# TestBoard2.net
KiCad netlist of a schematic drawn in EAGLE
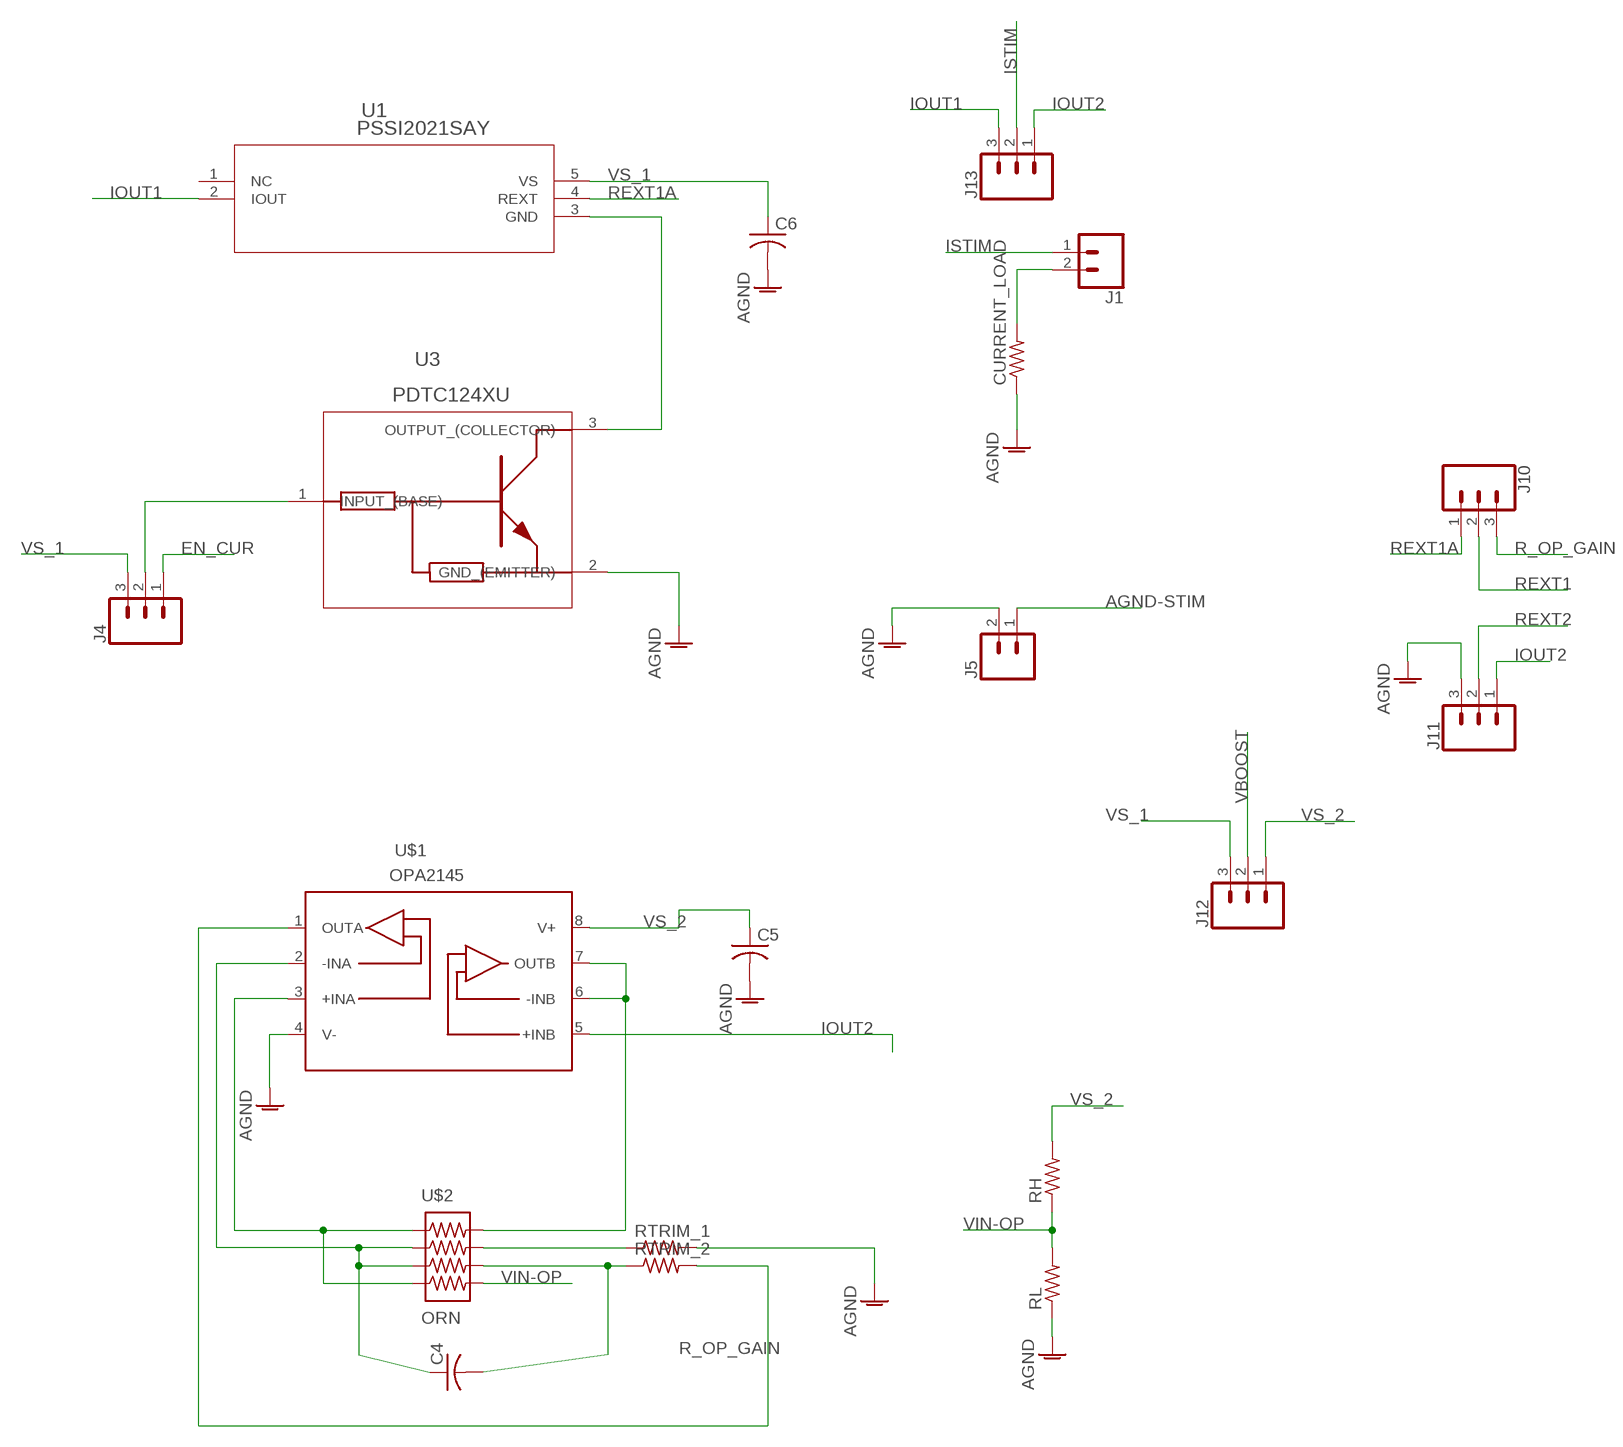
[diagram p0: schematic, sheet 1]
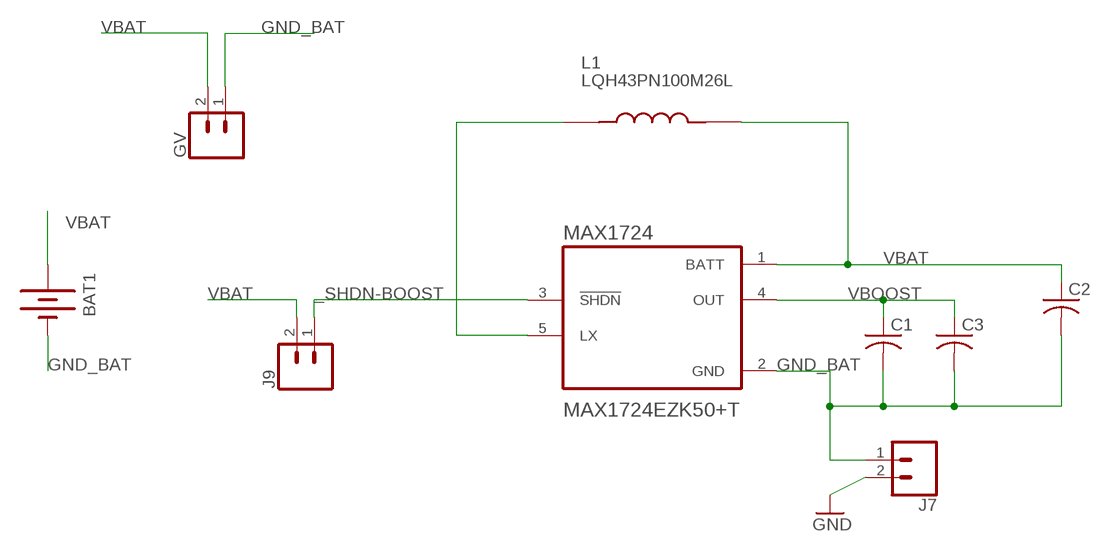
[diagram p1: schematic, sheet 2]
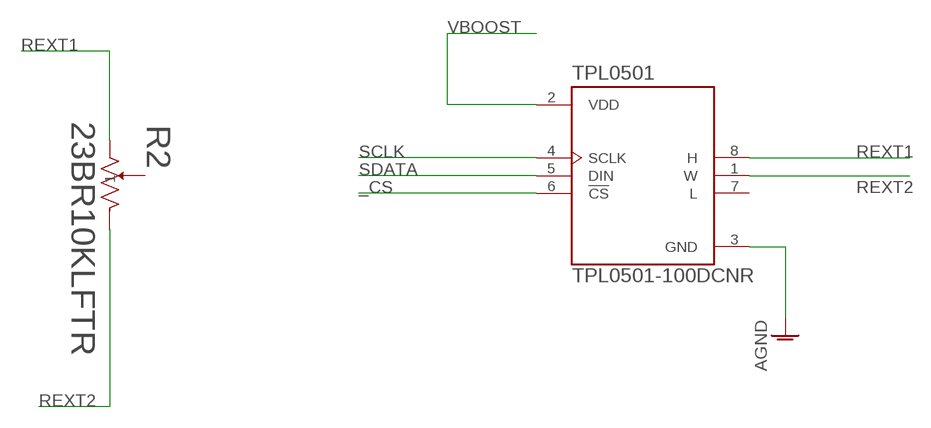
[diagram p2: schematic, sheet 3]
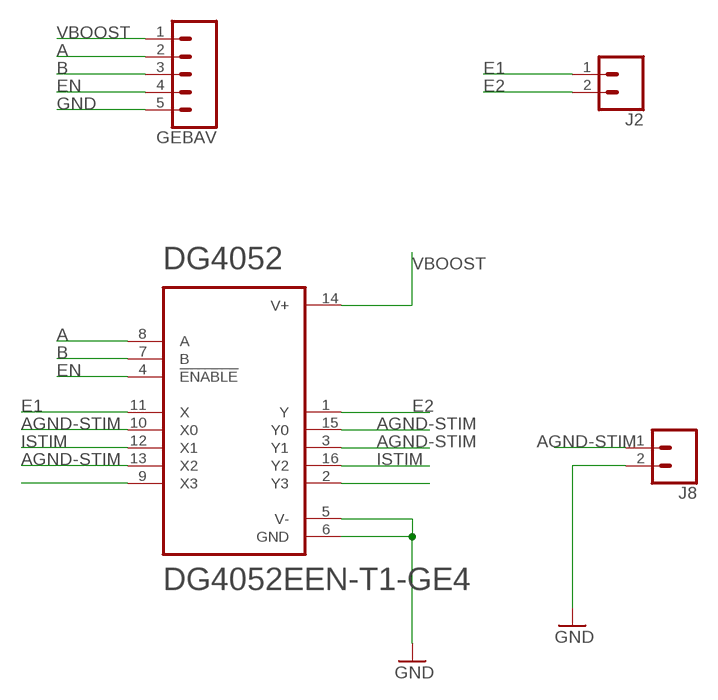
[diagram p3: schematic, sheet 4]
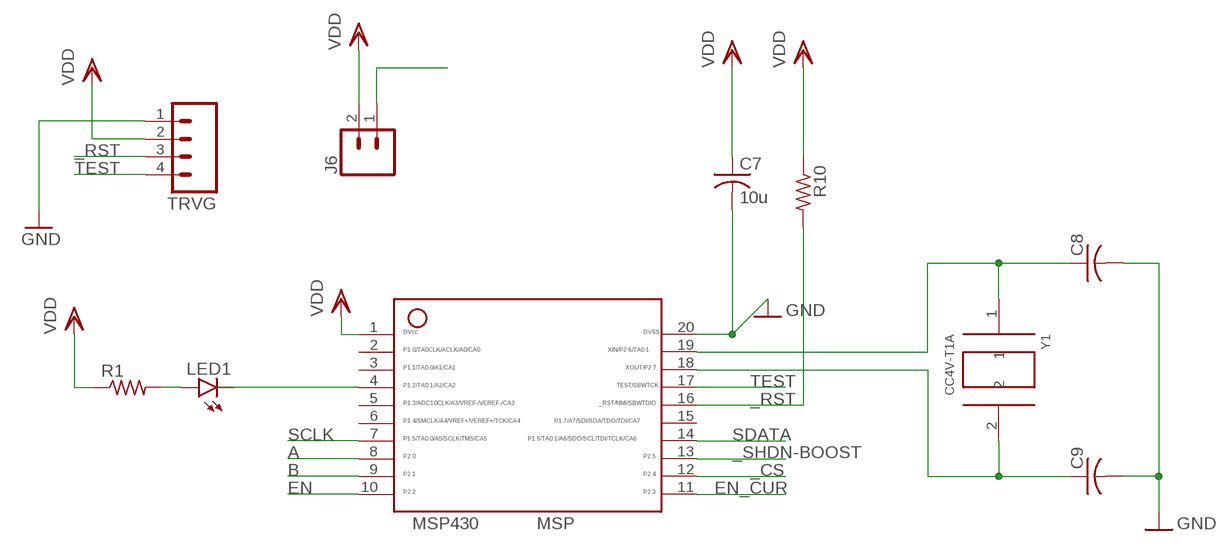
[diagram p4: schematic, sheet 5]

(export (version "E")
  (design (tool "Eeschema 10.0.6"))
  (components
    (comp (ref "BAT1")
      (value "BATTERYBU2032SM")
      (footprint "eagle-import:BU2032SM")
      (libsource (lib "eagle-import") (part "BATTERYBU2032SM"))
    )
    (comp (ref "C1")
      (value "C-USC1206")
      (footprint "eagle-import:C1206")
      (libsource (lib "eagle-import") (part "C-USC1206"))
    )
    (comp (ref "C2")
      (value "C-USC1206")
      (footprint "eagle-import:C1206")
      (libsource (lib "eagle-import") (part "C-USC1206"))
    )
    (comp (ref "C3")
      (value "C-USC0603")
      (footprint "eagle-import:C0603")
      (libsource (lib "eagle-import") (part "C-USC0603"))
    )
    (comp (ref "GV")
      (value "CONN_02")
      (footprint "eagle-import:1X02")
      (libsource (lib "eagle-import") (part "CONN_02"))
    )
    (comp (ref "J7")
      (value "CONN_02")
      (footprint "eagle-import:1X02")
      (libsource (lib "eagle-import") (part "CONN_02"))
    )
    (comp (ref "J9")
      (value "CONN_02")
      (footprint "eagle-import:1X02")
      (libsource (lib "eagle-import") (part "CONN_02"))
    )
    (comp (ref "L1")
      (value "LQH43PN100M26L")
      (footprint "eagle-import:IND_LQH43PN100M26L")
      (fields (field (name "DIGI-KEY_PART_NUMBER") "490-12780-1-ND") (field (name "MF") "Murata"))
      (libsource (lib "eagle-import") (part "LQH43PN100M26L"))
    )
    (comp (ref "MAX1724")
      (value "MAX1724EZK50+T")
      (footprint "eagle-import:SOT95P275X110-5N")
      (fields
        (field (name "DIGI-KEY_PART_NUMBER") "MAX1724EZK50+TCT-ND")
        (field (name "MF") "Maxim Integrated")
      )
      (libsource (lib "eagle-import") (part "MAX1724EZK50+T"))
    )
    (comp (ref "DG4052")
      (value "DG4052EEN-T1-GE4")
      (footprint "eagle-import:QFN40P260X180X60-16N")
      (fields (field (name "DIGI-KEY_PART_NUMBER") "DG4052EEN-T1-GE4CT-ND") (field (name "MF") "Vishay"))
      (libsource (lib "eagle-import") (part "DG4052EEN-T1-GE4"))
    )
    (comp (ref "GEBAV")
      (value "CONN_05LOCK")
      (footprint "eagle-import:1X05_LOCK")
      (libsource (lib "eagle-import") (part "CONN_05LOCK"))
    )
    (comp (ref "J2")
      (value "CONN_02")
      (footprint "eagle-import:1X02")
      (libsource (lib "eagle-import") (part "CONN_02"))
    )
    (comp (ref "J8")
      (value "CONN_02")
      (footprint "eagle-import:1X02")
      (libsource (lib "eagle-import") (part "CONN_02"))
    )
    (comp (ref "C4")
      (value "C-USC0603")
      (footprint "eagle-import:C0603")
      (libsource (lib "eagle-import") (part "C-USC0603"))
    )
    (comp (ref "C5")
      (value "C-USC0603")
      (footprint "eagle-import:C0603")
      (libsource (lib "eagle-import") (part "C-USC0603"))
    )
    (comp (ref "C6")
      (value "C-USC0603")
      (footprint "eagle-import:C0603")
      (libsource (lib "eagle-import") (part "C-USC0603"))
    )
    (comp (ref "CURRENT_LOAD")
      (value "R-US_0204/7")
      (footprint "eagle-import:0204_7")
      (libsource (lib "eagle-import") (part "R-US_0204/7"))
    )
    (comp (ref "J1")
      (value "CONN_02LOCK")
      (footprint "eagle-import:1X02_LOCK")
      (libsource (lib "eagle-import") (part "CONN_02LOCK"))
    )
    (comp (ref "J4")
      (value "CONN_03LOCK")
      (footprint "eagle-import:1X03_LOCK")
      (libsource (lib "eagle-import") (part "CONN_03LOCK"))
    )
    (comp (ref "J5")
      (value "CONN_02")
      (footprint "eagle-import:1X02")
      (libsource (lib "eagle-import") (part "CONN_02"))
    )
    (comp (ref "J10")
      (value "CONN_03")
      (footprint "eagle-import:1X03")
      (libsource (lib "eagle-import") (part "CONN_03"))
    )
    (comp (ref "J11")
      (value "CONN_03")
      (footprint "eagle-import:1X03")
      (libsource (lib "eagle-import") (part "CONN_03"))
    )
    (comp (ref "J12")
      (value "CONN_03LOCK")
      (footprint "eagle-import:1X03_LOCK")
      (libsource (lib "eagle-import") (part "CONN_03LOCK"))
    )
    (comp (ref "J13")
      (value "CONN_03LOCK")
      (footprint "eagle-import:1X03_LOCK")
      (libsource (lib "eagle-import") (part "CONN_03LOCK"))
    )
    (comp (ref "RH")
      (value "R-US_R0603")
      (footprint "eagle-import:R0603")
      (libsource (lib "eagle-import") (part "R-US_R0603"))
    )
    (comp (ref "RL")
      (value "R-US_R0603")
      (footprint "eagle-import:R0603")
      (libsource (lib "eagle-import") (part "R-US_R0603"))
    )
    (comp (ref "RTRIM_1")
      (value "R-US_R0603")
      (footprint "eagle-import:R0603")
      (libsource (lib "eagle-import") (part "R-US_R0603"))
    )
    (comp (ref "RTRIM_2")
      (value "R-US_R0603")
      (footprint "eagle-import:R0603")
      (libsource (lib "eagle-import") (part "R-US_R0603"))
    )
    (comp (ref "U$1")
      (value "OPA2145")
      (footprint "eagle-import:8-VSSOP")
      (libsource (lib "eagle-import") (part "OPA2145"))
    )
    (comp (ref "U$2")
      (value "ORN")
      (footprint "eagle-import:8-TSSOP")
      (libsource (lib "eagle-import") (part "ORN"))
    )
    (comp (ref "U1")
      (value "PSSI2021SAY")
      (footprint "eagle-import:SOT353_NXP")
      (fields (field (name "COPYRIGHT") "Copyright (C) 2021 Ultra Librarian. All rights reserved."))
      (libsource (lib "eagle-import") (part "PSSI2021SAY"))
    )
    (comp (ref "U3")
      (value "PDTC124XU")
      (footprint "eagle-import:SOT323_NXP")
      (fields (field (name "COPYRIGHT") "Copyright (C) 2021 Ultra Librarian. All rights reserved."))
      (libsource (lib "eagle-import") (part "PDTC124XU"))
    )
    (comp (ref "R2")
      (value "23BR10KLFTR")
      (footprint "eagle-import:RES3_23B_TTE")
      (fields (field (name "COPYRIGHT") "Copyright (C) 2016 Accelerated Designs. All rights reserved"))
      (libsource (lib "eagle-import") (part "23BR10KLFTR"))
    )
    (comp (ref "TPL0501")
      (value "TPL0501-100DCNR")
      (footprint "eagle-import:SOT65P280X145-8N")
      (fields (field (name "DIGI-KEY_PART_NUMBER") "296-29584-1-ND") (field (name "MF") "Texas Instruments"))
      (libsource (lib "eagle-import") (part "TPL0501-100DCNR"))
    )
    (comp (ref "C7")
      (value "10u")
      (footprint "eagle-import:C1206")
      (libsource (lib "eagle-import") (part "C-USC1206"))
    )
    (comp (ref "C8")
      (value "C-USC0603")
      (footprint "eagle-import:C0603")
      (libsource (lib "eagle-import") (part "C-USC0603"))
    )
    (comp (ref "C9")
      (value "C-USC0603")
      (footprint "eagle-import:C0603")
      (libsource (lib "eagle-import") (part "C-USC0603"))
    )
    (comp (ref "J6")
      (value "CONN_02")
      (footprint "eagle-import:1X02")
      (libsource (lib "eagle-import") (part "CONN_02"))
    )
    (comp (ref "LED1")
      (value "LEDCHIPLED_0603")
      (footprint "eagle-import:CHIPLED_0603")
      (libsource (lib "eagle-import") (part "LEDCHIPLED_0603"))
    )
    (comp (ref "MSP430")
      (value "MSP")
      (footprint "eagle-import:20_PIN")
      (libsource (lib "eagle-import") (part "MSP430"))
    )
    (comp (ref "R1")
      (value "R-US_R1206")
      (footprint "eagle-import:R1206")
      (libsource (lib "eagle-import") (part "R-US_R1206"))
    )
    (comp (ref "R10")
      (value "R-US_R1206")
      (footprint "eagle-import:R1206")
      (libsource (lib "eagle-import") (part "R-US_R1206"))
    )
    (comp (ref "TRVG")
      (value "M04LOCK")
      (footprint "eagle-import:1X04_LOCK")
      (libsource (lib "eagle-import") (part "M04LOCK"))
    )
    (comp (ref "Y1")
      (value "CC4V-T1A")
      (footprint "eagle-import:CC4V-T1A")
      (fields (field (name "MF") "Micro Crystal AG") (field (name "MP") "CC4V-T1A-32.768KHZ-7PF-20PPM"))
      (libsource (lib "eagle-import") (part "CC4V-T1A"))
    )
  )
  (nets
    (net (code "1") (name "A") (class "Default")
      (node (ref "DG4052") (pin "8") (pinfunction "A_8") (pintype "input"))
      (node (ref "GEBAV") (pin "2") (pinfunction "2_2") (pintype "passive"))
      (node (ref "MSP430") (pin "8") (pinfunction "8_8") (pintype "bidirectional"))
    )
    (net (code "2") (name "AGND") (class "Default")
      (node (ref "C5") (pin "2") (pinfunction "2_2") (pintype "passive"))
      (node (ref "C6") (pin "2") (pinfunction "2_2") (pintype "passive"))
      (node (ref "CURRENT_LOAD") (pin "1") (pinfunction "1_1") (pintype "passive"))
      (node (ref "J11") (pin "3") (pinfunction "3_3") (pintype "passive"))
      (node (ref "J5") (pin "2") (pinfunction "2_2") (pintype "passive"))
      (node (ref "RL") (pin "1") (pinfunction "1_1") (pintype "passive"))
      (node (ref "RTRIM_1") (pin "2") (pinfunction "2_2") (pintype "passive"))
      (node (ref "TPL0501") (pin "3") (pinfunction "GND_3") (pintype "power_in"))
      (node (ref "U$1") (pin "4") (pinfunction "V-_4") (pintype "bidirectional"))
      (node (ref "U3") (pin "2") (pinfunction "GND_(EMITTER)_2") (pintype "passive"))
    )
    (net (code "3") (name "AGND-STIM") (class "Default")
      (node (ref "DG4052") (pin "10") (pinfunction "X0_10") (pintype "passive"))
      (node (ref "DG4052") (pin "13") (pinfunction "X2_13") (pintype "passive"))
      (node (ref "DG4052") (pin "15") (pinfunction "Y0_15") (pintype "passive"))
      (node (ref "DG4052") (pin "3") (pinfunction "Y1_3") (pintype "passive"))
      (node (ref "J5") (pin "1") (pinfunction "1_1") (pintype "passive"))
      (node (ref "J8") (pin "1") (pinfunction "1_1") (pintype "passive"))
    )
    (net (code "4") (name "B") (class "Default")
      (node (ref "DG4052") (pin "7") (pinfunction "B_7") (pintype "input"))
      (node (ref "GEBAV") (pin "3") (pinfunction "3_3") (pintype "passive"))
      (node (ref "MSP430") (pin "9") (pinfunction "9_9") (pintype "bidirectional"))
    )
    (net (code "5") (name "E1") (class "Default")
      (node (ref "DG4052") (pin "11") (pinfunction "X_11") (pintype "passive"))
      (node (ref "J2") (pin "1") (pinfunction "1_1") (pintype "passive"))
    )
    (net (code "6") (name "E2") (class "Default")
      (node (ref "DG4052") (pin "1") (pinfunction "Y_1") (pintype "passive"))
      (node (ref "J2") (pin "2") (pinfunction "2_2") (pintype "passive"))
    )
    (net (code "7") (name "EN") (class "Default")
      (node (ref "DG4052") (pin "4") (pinfunction "~{ENABLE}_4") (pintype "input"))
      (node (ref "GEBAV") (pin "4") (pinfunction "4_4") (pintype "passive"))
      (node (ref "MSP430") (pin "10") (pinfunction "10_10") (pintype "bidirectional"))
    )
    (net (code "8") (name "EN_CUR") (class "Default")
      (node (ref "J4") (pin "1") (pinfunction "1_1") (pintype "passive"))
      (node (ref "MSP430") (pin "11") (pinfunction "11_11") (pintype "bidirectional"))
    )
    (net (code "9") (name "GND") (class "Default")
      (node (ref "C7") (pin "2") (pinfunction "2_2") (pintype "passive"))
      (node (ref "C8") (pin "2") (pinfunction "2_2") (pintype "passive"))
      (node (ref "C9") (pin "2") (pinfunction "2_2") (pintype "passive"))
      (node (ref "DG4052") (pin "5") (pinfunction "V-_5") (pintype "power_in"))
      (node (ref "DG4052") (pin "6") (pinfunction "GND_6") (pintype "power_in"))
      (node (ref "GEBAV") (pin "5") (pinfunction "5_5") (pintype "passive"))
      (node (ref "J7") (pin "2") (pinfunction "2_2") (pintype "passive"))
      (node (ref "J8") (pin "2") (pinfunction "2_2") (pintype "passive"))
      (node (ref "MSP430") (pin "20") (pinfunction "20_20") (pintype "bidirectional"))
      (node (ref "TRVG") (pin "1") (pinfunction "1_1") (pintype "passive"))
    )
    (net (code "10") (name "GND_BAT") (class "Default")
      (node (ref "BAT1") (pin "P$2") (pinfunction "-_P$2") (pintype "power_in"))
      (node (ref "C1") (pin "2") (pinfunction "2_2") (pintype "passive"))
      (node (ref "C2") (pin "2") (pinfunction "2_2") (pintype "passive"))
      (node (ref "C3") (pin "2") (pinfunction "2_2") (pintype "passive"))
      (node (ref "GV") (pin "1") (pinfunction "1_1") (pintype "passive"))
      (node (ref "J7") (pin "1") (pinfunction "1_1") (pintype "passive"))
      (node (ref "MAX1724") (pin "2") (pinfunction "GND_2") (pintype "power_in"))
    )
    (net (code "11") (name "IOUT1") (class "Default")
      (node (ref "J13") (pin "3") (pinfunction "3_3") (pintype "passive"))
      (node (ref "U1") (pin "2") (pinfunction "IOUT_2") (pintype "passive"))
    )
    (net (code "12") (name "IOUT2") (class "Default")
      (node (ref "J11") (pin "1") (pinfunction "1_1") (pintype "passive"))
      (node (ref "J13") (pin "1") (pinfunction "1_1") (pintype "passive"))
      (node (ref "U$1") (pin "5") (pinfunction "+INB_5") (pintype "bidirectional"))
    )
    (net (code "13") (name "ISTIM") (class "Default")
      (node (ref "DG4052") (pin "12") (pinfunction "X1_12") (pintype "passive"))
      (node (ref "DG4052") (pin "16") (pinfunction "Y2_16") (pintype "passive"))
      (node (ref "J1") (pin "1") (pinfunction "1_1") (pintype "passive"))
      (node (ref "J13") (pin "2") (pinfunction "2_2") (pintype "passive"))
    )
    (net (code "14") (name "Net-(C4-Pad2)") (class "Default")
      (node (ref "C4") (pin "2") (pinfunction "2_2") (pintype "passive"))
      (node (ref "RTRIM_2") (pin "1") (pinfunction "1_1") (pintype "passive"))
      (node (ref "U$2") (pin "6") (pinfunction "6_6") (pintype "passive"))
    )
    (net (code "15") (name "Net-(C8-Pad1)") (class "Default")
      (node (ref "C8") (pin "1") (pinfunction "1_1") (pintype "passive"))
      (node (ref "MSP430") (pin "19") (pinfunction "19_19") (pintype "bidirectional"))
      (node (ref "Y1") (pin "1") (pinfunction "1_1") (pintype "passive"))
    )
    (net (code "16") (name "Net-(C9-Pad1)") (class "Default")
      (node (ref "C9") (pin "1") (pinfunction "1_1") (pintype "passive"))
      (node (ref "MSP430") (pin "18") (pinfunction "18_18") (pintype "bidirectional"))
      (node (ref "Y1") (pin "2") (pinfunction "2_2") (pintype "passive"))
    )
    (net (code "17") (name "Net-(CURRENT_LOAD-Pad2)") (class "Default")
      (node (ref "CURRENT_LOAD") (pin "2") (pinfunction "2_2") (pintype "passive"))
      (node (ref "J1") (pin "2") (pinfunction "2_2") (pintype "passive"))
    )
    (net (code "18") (name "Net-(LED1-PadA)") (class "Default")
      (node (ref "LED1") (pin "A") (pinfunction "A_A") (pintype "passive"))
      (node (ref "R1") (pin "2") (pinfunction "2_2") (pintype "passive"))
    )
    (net (code "19") (name "Net-(LED1-PadC)") (class "Default")
      (node (ref "LED1") (pin "C") (pinfunction "C_C") (pintype "passive"))
      (node (ref "MSP430") (pin "4") (pinfunction "4_4") (pintype "bidirectional"))
    )
    (net (code "20") (name "Net-(MAX1724-LX)") (class "Default")
      (node (ref "L1") (pin "1") (pinfunction "1_1") (pintype "passive"))
      (node (ref "MAX1724") (pin "5") (pinfunction "LX_5") (pintype "bidirectional"))
    )
    (net (code "21") (name "Net-(RTRIM_1-Pad1)") (class "Default")
      (node (ref "RTRIM_1") (pin "1") (pinfunction "1_1") (pintype "passive"))
      (node (ref "U$2") (pin "7") (pinfunction "7_7") (pintype "passive"))
    )
    (net (code "22") (name "Net-(U$1-+INA)") (class "Default")
      (node (ref "U$1") (pin "3") (pinfunction "+INA_3") (pintype "bidirectional"))
      (node (ref "U$2") (pin "1") (pinfunction "1_1") (pintype "passive"))
      (node (ref "U$2") (pin "4") (pinfunction "4_4") (pintype "passive"))
    )
    (net (code "23") (name "Net-(U$1--INA)") (class "Default")
      (node (ref "C4") (pin "1") (pinfunction "1_1") (pintype "passive"))
      (node (ref "U$1") (pin "2") (pinfunction "-INA_2") (pintype "bidirectional"))
      (node (ref "U$2") (pin "2") (pinfunction "2_2") (pintype "passive"))
      (node (ref "U$2") (pin "3") (pinfunction "3_3") (pintype "passive"))
    )
    (net (code "24") (name "Net-(U$1--INB)") (class "Default")
      (node (ref "U$1") (pin "6") (pinfunction "-INB_6") (pintype "bidirectional"))
      (node (ref "U$1") (pin "7") (pinfunction "OUTB_7") (pintype "bidirectional"))
      (node (ref "U$2") (pin "8") (pinfunction "8_8") (pintype "passive"))
    )
    (net (code "25") (name "Net-(U1-GND)") (class "Default")
      (node (ref "U1") (pin "3") (pinfunction "GND_3") (pintype "passive"))
      (node (ref "U3") (pin "3") (pinfunction "OUTPUT_(COLLECTOR)_3") (pintype "passive"))
    )
    (net (code "26") (name "Net-(U3-INPUT_(BASE))") (class "Default")
      (node (ref "J4") (pin "2") (pinfunction "2_2") (pintype "passive"))
      (node (ref "U3") (pin "1") (pinfunction "INPUT_(BASE)_1") (pintype "passive"))
    )
    (net (code "27") (name "REXT1") (class "Default")
      (node (ref "J10") (pin "2") (pinfunction "2_2") (pintype "passive"))
      (node (ref "R2") (pin "1") (pinfunction "1_1") (pintype "passive"))
      (node (ref "TPL0501") (pin "8") (pinfunction "H_8") (pintype "bidirectional"))
    )
    (net (code "28") (name "REXT1A") (class "Default")
      (node (ref "J10") (pin "1") (pinfunction "1_1") (pintype "passive"))
      (node (ref "U1") (pin "4") (pinfunction "REXT_4") (pintype "passive"))
    )
    (net (code "29") (name "REXT2") (class "Default")
      (node (ref "J11") (pin "2") (pinfunction "2_2") (pintype "passive"))
      (node (ref "R2") (pin "3") (pinfunction "3_3") (pintype "passive"))
      (node (ref "TPL0501") (pin "1") (pinfunction "W_1") (pintype "bidirectional"))
    )
    (net (code "30") (name "R_OP_GAIN") (class "Default")
      (node (ref "J10") (pin "3") (pinfunction "3_3") (pintype "passive"))
      (node (ref "RTRIM_2") (pin "2") (pinfunction "2_2") (pintype "passive"))
      (node (ref "U$1") (pin "1") (pinfunction "OUTA_1") (pintype "bidirectional"))
    )
    (net (code "31") (name "SCLK") (class "Default")
      (node (ref "MSP430") (pin "7") (pinfunction "7_7") (pintype "bidirectional"))
      (node (ref "TPL0501") (pin "4") (pinfunction "SCLK_4") (pintype "input"))
    )
    (net (code "32") (name "SDATA") (class "Default")
      (node (ref "MSP430") (pin "14") (pinfunction "14_14") (pintype "bidirectional"))
      (node (ref "TPL0501") (pin "5") (pinfunction "DIN_5") (pintype "input"))
    )
    (net (code "33") (name "TEST") (class "Default")
      (node (ref "MSP430") (pin "17") (pinfunction "17_17") (pintype "bidirectional"))
      (node (ref "TRVG") (pin "4") (pinfunction "4_4") (pintype "passive"))
    )
    (net (code "34") (name "VBAT") (class "Default")
      (node (ref "BAT1") (pin "P$1") (pinfunction "+_P$1") (pintype "power_in"))
      (node (ref "C2") (pin "1") (pinfunction "1_1") (pintype "passive"))
      (node (ref "GV") (pin "2") (pinfunction "2_2") (pintype "passive"))
      (node (ref "J6") (pin "1") (pinfunction "1_1") (pintype "passive"))
      (node (ref "J9") (pin "2") (pinfunction "2_2") (pintype "passive"))
      (node (ref "L1") (pin "2") (pinfunction "2_2") (pintype "passive"))
      (node (ref "MAX1724") (pin "1") (pinfunction "BATT_1") (pintype "power_in"))
    )
    (net (code "35") (name "VBOOST") (class "Default")
      (node (ref "C1") (pin "1") (pinfunction "1_1") (pintype "passive"))
      (node (ref "C3") (pin "1") (pinfunction "1_1") (pintype "passive"))
      (node (ref "DG4052") (pin "14") (pinfunction "V+_14") (pintype "power_in"))
      (node (ref "GEBAV") (pin "1") (pinfunction "1_1") (pintype "passive"))
      (node (ref "J12") (pin "2") (pinfunction "2_2") (pintype "passive"))
      (node (ref "MAX1724") (pin "4") (pinfunction "OUT_4") (pintype "output"))
      (node (ref "TPL0501") (pin "2") (pinfunction "VDD_2") (pintype "power_in"))
    )
    (net (code "36") (name "VDD") (class "Default")
      (node (ref "C7") (pin "1") (pinfunction "1_1") (pintype "passive"))
      (node (ref "J6") (pin "2") (pinfunction "2_2") (pintype "passive"))
      (node (ref "MSP430") (pin "1") (pinfunction "1_1") (pintype "bidirectional"))
      (node (ref "R1") (pin "1") (pinfunction "1_1") (pintype "passive"))
      (node (ref "R10") (pin "1") (pinfunction "1_1") (pintype "passive"))
      (node (ref "TRVG") (pin "2") (pinfunction "2_2") (pintype "passive"))
    )
    (net (code "37") (name "VIN-OP") (class "Default")
      (node (ref "RH") (pin "1") (pinfunction "1_1") (pintype "passive"))
      (node (ref "RL") (pin "2") (pinfunction "2_2") (pintype "passive"))
      (node (ref "U$2") (pin "5") (pinfunction "5_5") (pintype "passive"))
    )
    (net (code "38") (name "VS_1") (class "Default")
      (node (ref "C6") (pin "1") (pinfunction "1_1") (pintype "passive"))
      (node (ref "J12") (pin "3") (pinfunction "3_3") (pintype "passive"))
      (node (ref "J4") (pin "3") (pinfunction "3_3") (pintype "passive"))
      (node (ref "U1") (pin "5") (pinfunction "VS_5") (pintype "passive"))
    )
    (net (code "39") (name "VS_2") (class "Default")
      (node (ref "C5") (pin "1") (pinfunction "1_1") (pintype "passive"))
      (node (ref "J12") (pin "1") (pinfunction "1_1") (pintype "passive"))
      (node (ref "RH") (pin "2") (pinfunction "2_2") (pintype "passive"))
      (node (ref "U$1") (pin "8") (pinfunction "V+_8") (pintype "bidirectional"))
    )
    (net (code "40") (name "_CS") (class "Default")
      (node (ref "MSP430") (pin "12") (pinfunction "12_12") (pintype "bidirectional"))
      (node (ref "TPL0501") (pin "6") (pinfunction "~{CS}_6") (pintype "input"))
    )
    (net (code "41") (name "_RST") (class "Default")
      (node (ref "MSP430") (pin "16") (pinfunction "16_16") (pintype "bidirectional"))
      (node (ref "R10") (pin "2") (pinfunction "2_2") (pintype "passive"))
      (node (ref "TRVG") (pin "3") (pinfunction "3_3") (pintype "passive"))
    )
    (net (code "42") (name "_SHDN-BOOST") (class "Default")
      (node (ref "J9") (pin "1") (pinfunction "1_1") (pintype "passive"))
      (node (ref "MAX1724") (pin "3") (pinfunction "~{SHDN}_3") (pintype "input"))
      (node (ref "MSP430") (pin "13") (pinfunction "13_13") (pintype "bidirectional"))
    )
    (net (code "43") (name "unconnected-(DG4052-X3-Pad9)") (class "Default")
      (node (ref "DG4052") (pin "9") (pinfunction "X3_9") (pintype "passive"))
    )
    (net (code "44") (name "unconnected-(DG4052-Y3-Pad2)") (class "Default")
      (node (ref "DG4052") (pin "2") (pinfunction "Y3_2") (pintype "passive"))
    )
    (net (code "45") (name "unconnected-(MSP430-Pad2)") (class "Default")
      (node (ref "MSP430") (pin "2") (pinfunction "2_2") (pintype "bidirectional"))
    )
    (net (code "46") (name "unconnected-(MSP430-Pad3)") (class "Default")
      (node (ref "MSP430") (pin "3") (pinfunction "3_3") (pintype "bidirectional"))
    )
    (net (code "47") (name "unconnected-(MSP430-Pad5)") (class "Default")
      (node (ref "MSP430") (pin "5") (pinfunction "5_5") (pintype "bidirectional"))
    )
    (net (code "48") (name "unconnected-(MSP430-Pad6)") (class "Default")
      (node (ref "MSP430") (pin "6") (pinfunction "6_6") (pintype "bidirectional"))
    )
    (net (code "49") (name "unconnected-(MSP430-Pad15)") (class "Default")
      (node (ref "MSP430") (pin "15") (pinfunction "15_15") (pintype "bidirectional"))
    )
    (net (code "50") (name "unconnected-(R2-Pad2)") (class "Default")
      (node (ref "R2") (pin "2") (pinfunction "2_2") (pintype "passive"))
    )
    (net (code "51") (name "unconnected-(TPL0501-L-Pad7)") (class "Default")
      (node (ref "TPL0501") (pin "7") (pinfunction "L_7") (pintype "bidirectional"))
    )
    (net (code "52") (name "unconnected-(U1-NC-Pad1)") (class "Default")
      (node (ref "U1") (pin "1") (pinfunction "NC_1") (pintype "passive"))
    )
  )
)
